# LAMEBOY.net
KiCad netlist of a schematic drawn in EAGLE
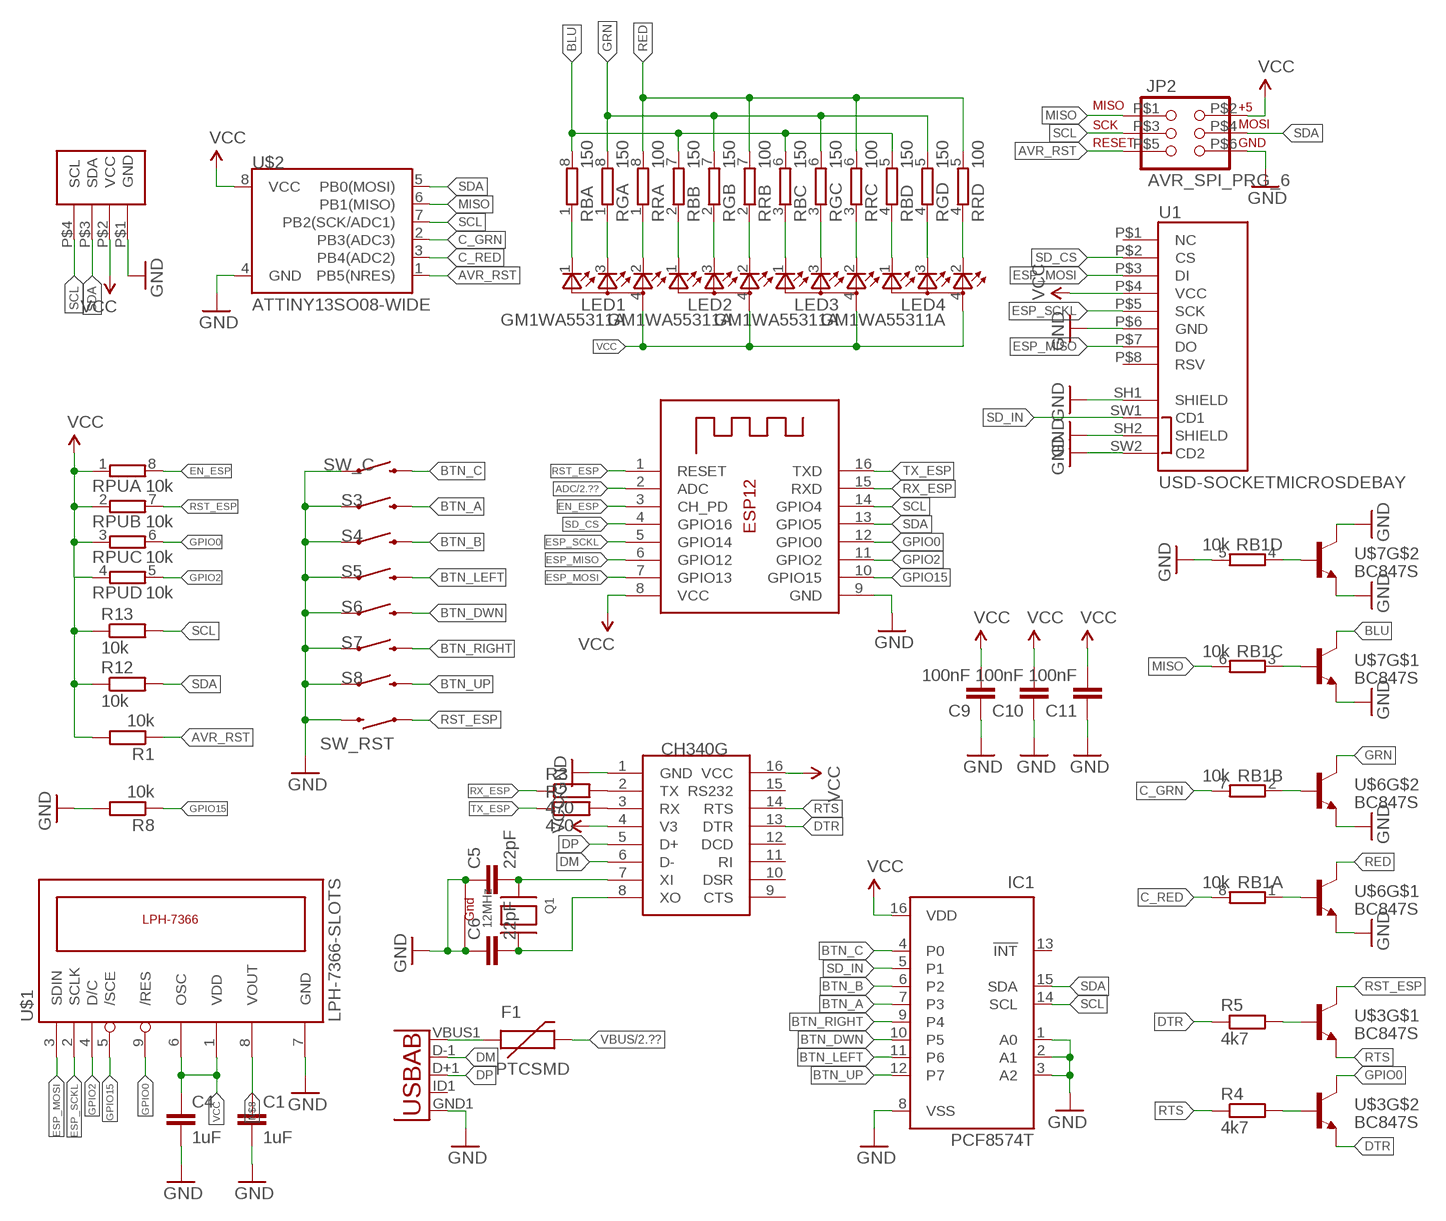
[diagram p0: schematic, sheet 1]
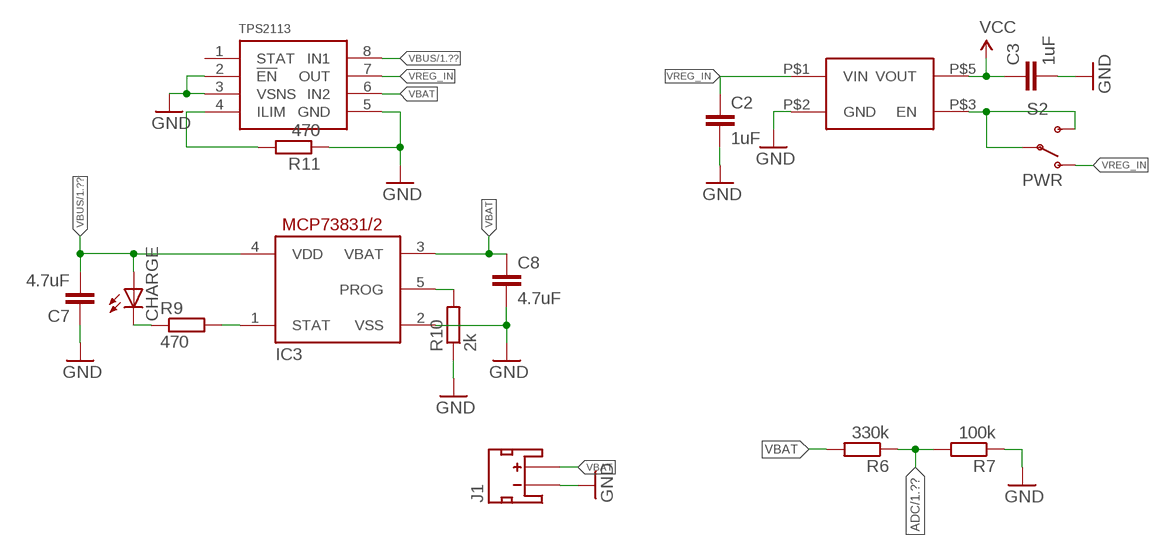
[diagram p1: schematic, sheet 2]

(export (version "E")
  (design (tool "Eeschema 10.0.6"))
  (components
    (comp (ref "C2")
      (value "1uF")
      (footprint "eagle-import:ONEFITSALL")
      (libsource (lib "eagle-import") (part "C-EUONEFITSALL"))
    )
    (comp (ref "C3")
      (value "1uF")
      (footprint "eagle-import:ONEFITSALL")
      (libsource (lib "eagle-import") (part "C-EUONEFITSALL"))
    )
    (comp (ref "C7")
      (value "4.7uF")
      (footprint "eagle-import:ONEFITSALL")
      (libsource (lib "eagle-import") (part "C-EUONEFITSALL"))
    )
    (comp (ref "C8")
      (value "4.7uF")
      (footprint "eagle-import:ONEFITSALL")
      (libsource (lib "eagle-import") (part "C-EUONEFITSALL"))
    )
    (comp (ref "CHARGE")
      (value "LEDCHARLIE")
      (footprint "eagle-import:CHIPLED_0603_CHARLIE")
      (libsource (lib "eagle-import") (part "LEDCHARLIE"))
    )
    (comp (ref "IC3")
      (value "MCP73831")
      (footprint "eagle-import:SOT23-5L")
      (libsource (lib "eagle-import") (part "MCP73831/OT"))
    )
    (comp (ref "J1")
      (value "JST_2MM_MALE")
      (footprint "eagle-import:JST-2-SMD")
      (libsource (lib "eagle-import") (part "JST_2MM_MALE"))
    )
    (comp (ref "R6")
      (value "330k")
      (footprint "eagle-import:ONEFITSALL")
      (libsource (lib "eagle-import") (part "R-EU_ONEFITSALL"))
    )
    (comp (ref "R7")
      (value "100k")
      (footprint "eagle-import:ONEFITSALL")
      (libsource (lib "eagle-import") (part "R-EU_ONEFITSALL"))
    )
    (comp (ref "R9")
      (value "470")
      (footprint "eagle-import:ONEFITSALL")
      (libsource (lib "eagle-import") (part "R-EU_ONEFITSALL"))
    )
    (comp (ref "R10")
      (value "2k")
      (footprint "eagle-import:ONEFITSALL")
      (libsource (lib "eagle-import") (part "R-EU_ONEFITSALL"))
    )
    (comp (ref "R11")
      (value "470")
      (footprint "eagle-import:ONEFITSALL")
      (libsource (lib "eagle-import") (part "R-EU_ONEFITSALL"))
    )
    (comp (ref "S2")
      (value "PWR")
      (footprint "eagle-import:SWITCH-SPST-SMD-A")
      (libsource (lib "eagle-import") (part "SWITCH-SPDT-SMD-A"))
    )
    (comp (ref "U$4")
      (value "TPS2113-PW")
      (footprint "eagle-import:TEXAS-PW")
      (libsource (lib "eagle-import") (part "TPS2113-PW"))
    )
    (comp (ref "U$9")
      (value "AP2112KAP2112K")
      (footprint "eagle-import:AP2112")
      (libsource (lib "eagle-import") (part "AP2112KAP2112K"))
    )
    (comp (ref "C1")
      (value "1uF")
      (footprint "eagle-import:ONEFITSALL")
      (libsource (lib "eagle-import") (part "C-EUONEFITSALL"))
    )
    (comp (ref "C4")
      (value "1uF")
      (footprint "eagle-import:ONEFITSALL")
      (libsource (lib "eagle-import") (part "C-EUONEFITSALL"))
    )
    (comp (ref "C5")
      (value "22pF")
      (footprint "eagle-import:ONEFITSALL")
      (libsource (lib "eagle-import") (part "C-EUONEFITSALL"))
    )
    (comp (ref "C6")
      (value "22pF")
      (footprint "eagle-import:ONEFITSALL")
      (libsource (lib "eagle-import") (part "C-EUONEFITSALL"))
    )
    (comp (ref "C9")
      (value "100nF")
      (footprint "eagle-import:ONEFITSALL")
      (libsource (lib "eagle-import") (part "C-EUONEFITSALL"))
    )
    (comp (ref "C10")
      (value "100nF")
      (footprint "eagle-import:ONEFITSALL")
      (libsource (lib "eagle-import") (part "C-EUONEFITSALL"))
    )
    (comp (ref "C11")
      (value "100nF")
      (footprint "eagle-import:ONEFITSALL")
      (libsource (lib "eagle-import") (part "C-EUONEFITSALL"))
    )
    (comp (ref "CH340G")
      (value "CH340GCH340G")
      (footprint "eagle-import:SOIC16")
      (libsource (lib "eagle-import") (part "CH340GCH340G"))
    )
    (comp (ref "F1")
      (value "PTCSMD")
      (footprint "eagle-import:PTC-1206")
      (libsource (lib "eagle-import") (part "PTCSMD"))
    )
    (comp (ref "IC1")
      (value "PCF8574T")
      (footprint "eagle-import:SO16W")
      (fields (field (name "MPN") "PCF8574T/3,512"))
      (libsource (lib "eagle-import") (part "PCF8574T"))
    )
    (comp (ref "JP2")
      (value "AVR_SPI_PRG_6")
      (footprint "eagle-import:2X3_SMD_PAD")
      (libsource (lib "eagle-import") (part "AVR_SPI_PRG_6"))
    )
    (comp (ref "LED1")
      (value "GM1WA55311A")
      (footprint "eagle-import:GM1WA55311A")
      (libsource (lib "eagle-import") (part "GM1WA55311A"))
    )
    (comp (ref "LED2")
      (value "GM1WA55311A")
      (footprint "eagle-import:GM1WA55311A")
      (libsource (lib "eagle-import") (part "GM1WA55311A"))
    )
    (comp (ref "LED3")
      (value "GM1WA55311A")
      (footprint "eagle-import:GM1WA55311A")
      (libsource (lib "eagle-import") (part "GM1WA55311A"))
    )
    (comp (ref "LED4")
      (value "GM1WA55311A")
      (footprint "eagle-import:GM1WA55311A")
      (libsource (lib "eagle-import") (part "GM1WA55311A"))
    )
    (comp (ref "Q1")
      (value "12MHz")
      (footprint "eagle-import:NX3225_BIGGER")
      (libsource (lib "eagle-import") (part "XTAL-4BIGGER"))
    )
    (comp (ref "R1")
      (value "10k")
      (footprint "eagle-import:ONEFITSALL")
      (libsource (lib "eagle-import") (part "R-EU_ONEFITSALL"))
    )
    (comp (ref "R2")
      (value "470")
      (footprint "eagle-import:ONEFITSALL")
      (libsource (lib "eagle-import") (part "R-EU_ONEFITSALL"))
    )
    (comp (ref "R3")
      (value "470")
      (footprint "eagle-import:ONEFITSALL")
      (libsource (lib "eagle-import") (part "R-EU_ONEFITSALL"))
    )
    (comp (ref "R4")
      (value "4k7")
      (footprint "eagle-import:ONEFITSALL")
      (libsource (lib "eagle-import") (part "R-EU_ONEFITSALL"))
    )
    (comp (ref "R5")
      (value "4k7")
      (footprint "eagle-import:ONEFITSALL")
      (libsource (lib "eagle-import") (part "R-EU_ONEFITSALL"))
    )
    (comp (ref "R8")
      (value "10k")
      (footprint "eagle-import:ONEFITSALL")
      (libsource (lib "eagle-import") (part "R-EU_ONEFITSALL"))
    )
    (comp (ref "R12")
      (value "10k")
      (footprint "eagle-import:ONEFITSALL")
      (libsource (lib "eagle-import") (part "R-EU_ONEFITSALL"))
    )
    (comp (ref "R13")
      (value "10k")
      (footprint "eagle-import:ONEFITSALL")
      (libsource (lib "eagle-import") (part "R-EU_ONEFITSALL"))
    )
    (comp (ref "RB")
      (value "150")
      (footprint "eagle-import:0603-ARC")
      (libsource (lib "eagle-import") (part "4R-N0603-ARC"))
    )
    (comp (ref "RB1")
      (value "10k")
      (footprint "eagle-import:0603-ARC")
      (libsource (lib "eagle-import") (part "4R-N0603-ARC"))
    )
    (comp (ref "RG")
      (value "150")
      (footprint "eagle-import:0603-ARC")
      (libsource (lib "eagle-import") (part "4R-N0603-ARC"))
    )
    (comp (ref "RPU")
      (value "10k")
      (footprint "eagle-import:0603-ARC")
      (libsource (lib "eagle-import") (part "4R-N0603-ARC"))
    )
    (comp (ref "RR")
      (value "100")
      (footprint "eagle-import:0603-ARC")
      (libsource (lib "eagle-import") (part "4R-N0603-ARC"))
    )
    (comp (ref "S3")
      (value "SWITCH-MOMENTARY-2SMD-4")
      (footprint "eagle-import:TACTILE_SWITCH_TALL")
      (libsource (lib "eagle-import") (part "SWITCH-MOMENTARY-2SMD-4"))
    )
    (comp (ref "S4")
      (value "SWITCH-MOMENTARY-2SMD-4")
      (footprint "eagle-import:TACTILE_SWITCH_TALL")
      (libsource (lib "eagle-import") (part "SWITCH-MOMENTARY-2SMD-4"))
    )
    (comp (ref "S5")
      (value "SWITCH-MOMENTARY-2SMD-4")
      (footprint "eagle-import:TACTILE_SWITCH_TALL")
      (libsource (lib "eagle-import") (part "SWITCH-MOMENTARY-2SMD-4"))
    )
    (comp (ref "S6")
      (value "SWITCH-MOMENTARY-2SMD-4")
      (footprint "eagle-import:TACTILE_SWITCH_TALL")
      (libsource (lib "eagle-import") (part "SWITCH-MOMENTARY-2SMD-4"))
    )
    (comp (ref "S7")
      (value "SWITCH-MOMENTARY-2SMD-4")
      (footprint "eagle-import:TACTILE_SWITCH_TALL")
      (libsource (lib "eagle-import") (part "SWITCH-MOMENTARY-2SMD-4"))
    )
    (comp (ref "S8")
      (value "SWITCH-MOMENTARY-2SMD-4")
      (footprint "eagle-import:TACTILE_SWITCH_TALL")
      (libsource (lib "eagle-import") (part "SWITCH-MOMENTARY-2SMD-4"))
    )
    (comp (ref "SW_C")
      (value "SWITCH-MOMENTARY-2-SMD-1101NE")
      (footprint "eagle-import:TACTILE-SWITCH-1101NE")
      (libsource (lib "eagle-import") (part "SWITCH-MOMENTARY-2-SMD-1101NE"))
    )
    (comp (ref "SW_RST")
      (value "SWITCH-MOMENTARY-2-SMD-1101NE")
      (footprint "eagle-import:TACTILE-SWITCH-1101NE")
      (libsource (lib "eagle-import") (part "SWITCH-MOMENTARY-2-SMD-1101NE"))
    )
    (comp (ref "U$1")
      (value "LPH-7366-SLOTS")
      (footprint "eagle-import:LPH-7366-SLOTS")
      (libsource (lib "eagle-import") (part "LPH-7366-SLOTS"))
    )
    (comp (ref "U$2")
      (value "ATTINY13SO08-WIDE")
      (footprint "eagle-import:SO08-EIAJ")
      (libsource (lib "eagle-import") (part "ATTINY13SO08-WIDE"))
    )
    (comp (ref "U$3")
      (value "BC847S")
      (footprint "eagle-import:SOT363")
      (libsource (lib "eagle-import") (part "MMDT3904"))
    )
    (comp (ref "U$6")
      (value "BC847S")
      (footprint "eagle-import:SOT363")
      (libsource (lib "eagle-import") (part "MMDT3904"))
    )
    (comp (ref "U$7")
      (value "BC847S")
      (footprint "eagle-import:SOT363")
      (libsource (lib "eagle-import") (part "MMDT3904"))
    )
    (comp (ref "U$10")
      (value "I2C_GROVE")
      (footprint "eagle-import:I2C_GROVE")
      (libsource (lib "eagle-import") (part "I2C_GROVE"))
    )
    (comp (ref "U1")
      (value "USD-SOCKETMICROSDEBAY")
      (footprint "eagle-import:MICRO-SD-SOCKET-EBAY")
      (libsource (lib "eagle-import") (part "USD-SOCKETMICROSDEBAY"))
    )
    (comp (ref "U2")
      (value "USB")
      (footprint "eagle-import:USB-AB-MICRO-SMD_V03")
      (libsource (lib "eagle-import") (part "USB-ABCONN-11794"))
    )
    (comp (ref "X1")
      (value "ESP-12")
      (footprint "eagle-import:ESP-12")
      (libsource (lib "eagle-import") (part "ESP-12"))
    )
  )
  (nets
    (net (code "1") (name "ADC") (class "Default")
      (node (ref "R6") (pin "P$1") (pinfunction "1_P$1") (pintype "passive"))
      (node (ref "R7") (pin "P$2") (pinfunction "2_P$2") (pintype "passive"))
      (node (ref "X1") (pin "2") (pinfunction "ADC_2") (pintype "passive"))
    )
    (net (code "2") (name "AVR_RST") (class "Default")
      (node (ref "JP2") (pin "P$5") (pinfunction "5_P$5") (pintype "passive"))
      (node (ref "R1") (pin "P$1") (pinfunction "1_P$1") (pintype "passive"))
      (node (ref "U$2") (pin "1") (pinfunction "PB5(NRES)_1") (pintype "bidirectional"))
    )
    (net (code "3") (name "BLU") (class "Default")
      (node (ref "RB") (pin "5") (pinfunction "2_5") (pintype "passive"))
      (node (ref "RB") (pin "6") (pinfunction "2_6") (pintype "passive"))
      (node (ref "RB") (pin "7") (pinfunction "2_7") (pintype "passive"))
      (node (ref "RB") (pin "8") (pinfunction "2_8") (pintype "passive"))
      (node (ref "U$7") (pin "3") (pinfunction "C_3") (pintype "passive"))
    )
    (net (code "4") (name "BTN_A") (class "Default")
      (node (ref "IC1") (pin "7") (pinfunction "P3_7") (pintype "bidirectional"))
      (node (ref "S3") (pin "B2") (pinfunction "2_B2") (pintype "passive"))
    )
    (net (code "5") (name "BTN_B") (class "Default")
      (node (ref "IC1") (pin "6") (pinfunction "P2_6") (pintype "bidirectional"))
      (node (ref "S4") (pin "B2") (pinfunction "2_B2") (pintype "passive"))
    )
    (net (code "6") (name "BTN_C") (class "Default")
      (node (ref "IC1") (pin "4") (pinfunction "P0_4") (pintype "bidirectional"))
      (node (ref "SW_C") (pin "P$2") (pinfunction "2_P$2") (pintype "passive"))
    )
    (net (code "7") (name "BTN_DWN") (class "Default")
      (node (ref "IC1") (pin "10") (pinfunction "P5_10") (pintype "bidirectional"))
      (node (ref "S6") (pin "B2") (pinfunction "2_B2") (pintype "passive"))
    )
    (net (code "8") (name "BTN_LEFT") (class "Default")
      (node (ref "IC1") (pin "11") (pinfunction "P6_11") (pintype "bidirectional"))
      (node (ref "S5") (pin "B2") (pinfunction "2_B2") (pintype "passive"))
    )
    (net (code "9") (name "BTN_RIGHT") (class "Default")
      (node (ref "IC1") (pin "9") (pinfunction "P4_9") (pintype "bidirectional"))
      (node (ref "S7") (pin "B2") (pinfunction "2_B2") (pintype "passive"))
    )
    (net (code "10") (name "BTN_UP") (class "Default")
      (node (ref "IC1") (pin "12") (pinfunction "P7_12") (pintype "bidirectional"))
      (node (ref "S8") (pin "B2") (pinfunction "2_B2") (pintype "passive"))
    )
    (net (code "11") (name "C_GRN") (class "Default")
      (node (ref "RB1") (pin "7") (pinfunction "2_7") (pintype "passive"))
      (node (ref "U$2") (pin "2") (pinfunction "PB3(ADC3)_2") (pintype "bidirectional"))
    )
    (net (code "12") (name "C_RED") (class "Default")
      (node (ref "RB1") (pin "8") (pinfunction "2_8") (pintype "passive"))
      (node (ref "U$2") (pin "3") (pinfunction "PB4(ADC2)_3") (pintype "bidirectional"))
    )
    (net (code "13") (name "DM") (class "Default")
      (node (ref "CH340G") (pin "6") (pinfunction "D-_6") (pintype "bidirectional"))
      (node (ref "U2") (pin "D-1") (pinfunction "D-_D-1") (pintype "bidirectional"))
    )
    (net (code "14") (name "DP") (class "Default")
      (node (ref "CH340G") (pin "5") (pinfunction "D+_5") (pintype "bidirectional"))
      (node (ref "U2") (pin "D+1") (pinfunction "D+_D+1") (pintype "bidirectional"))
    )
    (net (code "15") (name "DTR") (class "Default")
      (node (ref "CH340G") (pin "13") (pinfunction "DTR_13") (pintype "bidirectional"))
      (node (ref "R5") (pin "P$1") (pinfunction "1_P$1") (pintype "passive"))
      (node (ref "U$3") (pin "1") (pinfunction "E_1") (pintype "passive"))
    )
    (net (code "16") (name "EN_ESP") (class "Default")
      (node (ref "RPU") (pin "8") (pinfunction "2_8") (pintype "passive"))
      (node (ref "X1") (pin "3") (pinfunction "CH_PD_3") (pintype "input"))
    )
    (net (code "17") (name "ESP_MISO") (class "Default")
      (node (ref "U1") (pin "P$7") (pinfunction "DO_P$7") (pintype "bidirectional"))
      (node (ref "X1") (pin "6") (pinfunction "GPIO12_6") (pintype "bidirectional"))
    )
    (net (code "18") (name "ESP_MOSI") (class "Default")
      (node (ref "U$1") (pin "3") (pinfunction "SDIN_3") (pintype "input"))
      (node (ref "U1") (pin "P$3") (pinfunction "DI_P$3") (pintype "bidirectional"))
      (node (ref "X1") (pin "7") (pinfunction "GPIO13_7") (pintype "bidirectional"))
    )
    (net (code "19") (name "ESP_SCKL") (class "Default")
      (node (ref "U$1") (pin "2") (pinfunction "SCLK_2") (pintype "input"))
      (node (ref "U1") (pin "P$5") (pinfunction "SCK_P$5") (pintype "bidirectional"))
      (node (ref "X1") (pin "5") (pinfunction "GPIO14_5") (pintype "bidirectional"))
    )
    (net (code "20") (name "GND") (class "Default")
      (node (ref "C1") (pin "P$2") (pinfunction "2_P$2") (pintype "passive"))
      (node (ref "C10") (pin "P$1") (pinfunction "1_P$1") (pintype "passive"))
      (node (ref "C11") (pin "P$1") (pinfunction "1_P$1") (pintype "passive"))
      (node (ref "C2") (pin "P$2") (pinfunction "2_P$2") (pintype "passive"))
      (node (ref "C3") (pin "P$2") (pinfunction "2_P$2") (pintype "passive"))
      (node (ref "C4") (pin "P$2") (pinfunction "2_P$2") (pintype "passive"))
      (node (ref "C5") (pin "P$1") (pinfunction "1_P$1") (pintype "passive"))
      (node (ref "C6") (pin "P$1") (pinfunction "1_P$1") (pintype "passive"))
      (node (ref "C7") (pin "P$1") (pinfunction "1_P$1") (pintype "passive"))
      (node (ref "C8") (pin "P$2") (pinfunction "2_P$2") (pintype "passive"))
      (node (ref "C9") (pin "P$1") (pinfunction "1_P$1") (pintype "passive"))
      (node (ref "CH340G") (pin "1") (pinfunction "GND_1") (pintype "bidirectional"))
      (node (ref "IC1") (pin "1") (pinfunction "A0_1") (pintype "input"))
      (node (ref "IC1") (pin "2") (pinfunction "A1_2") (pintype "input"))
      (node (ref "IC1") (pin "3") (pinfunction "A2_3") (pintype "input"))
      (node (ref "IC1") (pin "8") (pinfunction "VSS_8") (pintype "power_in"))
      (node (ref "IC3") (pin "2") (pinfunction "VSS_2") (pintype "power_in"))
      (node (ref "J1") (pin "1") (pinfunction "-_1") (pintype "bidirectional"))
      (node (ref "JP2") (pin "P$6") (pinfunction "6_P$6") (pintype "passive"))
      (node (ref "Q1") (pin "2") (pinfunction "G2_2") (pintype "power_in"))
      (node (ref "Q1") (pin "4") (pinfunction "G1_4") (pintype "power_in"))
      (node (ref "R10") (pin "P$1") (pinfunction "1_P$1") (pintype "passive"))
      (node (ref "R11") (pin "P$1") (pinfunction "1_P$1") (pintype "passive"))
      (node (ref "R7") (pin "P$1") (pinfunction "1_P$1") (pintype "passive"))
      (node (ref "R8") (pin "P$2") (pinfunction "2_P$2") (pintype "passive"))
      (node (ref "RB1") (pin "5") (pinfunction "2_5") (pintype "passive"))
      (node (ref "S3") (pin "A2") (pinfunction "1_A2") (pintype "passive"))
      (node (ref "S4") (pin "A2") (pinfunction "1_A2") (pintype "passive"))
      (node (ref "S5") (pin "A2") (pinfunction "1_A2") (pintype "passive"))
      (node (ref "S6") (pin "A2") (pinfunction "1_A2") (pintype "passive"))
      (node (ref "S7") (pin "A2") (pinfunction "1_A2") (pintype "passive"))
      (node (ref "S8") (pin "A2") (pinfunction "1_A2") (pintype "passive"))
      (node (ref "SW_C") (pin "P$1") (pinfunction "1_P$1") (pintype "passive"))
      (node (ref "SW_RST") (pin "P$2") (pinfunction "2_P$2") (pintype "passive"))
      (node (ref "U$1") (pin "7") (pinfunction "GND_7") (pintype "power_in"))
      (node (ref "U$10") (pin "P$1") (pinfunction "GND_P$1") (pintype "bidirectional"))
      (node (ref "U$2") (pin "4") (pinfunction "GND_4") (pintype "bidirectional"))
      (node (ref "U$4") (pin "2") (pinfunction "~{EN}_2") (pintype "bidirectional"))
      (node (ref "U$4") (pin "3") (pinfunction "VSNS_3") (pintype "bidirectional"))
      (node (ref "U$4") (pin "5") (pinfunction "GND_5") (pintype "bidirectional"))
      (node (ref "U$6") (pin "1") (pinfunction "E_1") (pintype "passive"))
      (node (ref "U$6") (pin "4") (pinfunction "E_4") (pintype "passive"))
      (node (ref "U$7") (pin "1") (pinfunction "E_1") (pintype "passive"))
      (node (ref "U$7") (pin "4") (pinfunction "E_4") (pintype "passive"))
      (node (ref "U$7") (pin "6") (pinfunction "C_6") (pintype "passive"))
      (node (ref "U$9") (pin "P$2") (pinfunction "GND_P$2") (pintype "bidirectional"))
      (node (ref "U1") (pin "P$6") (pinfunction "GND_P$6") (pintype "bidirectional"))
      (node (ref "U1") (pin "SH1") (pinfunction "SHIELD_SH1") (pintype "bidirectional"))
      (node (ref "U1") (pin "SH2") (pinfunction "SHIELD_SH2") (pintype "bidirectional"))
      (node (ref "U1") (pin "SW2") (pinfunction "CD2_SW2") (pintype "bidirectional"))
      (node (ref "U2") (pin "GND1") (pinfunction "GND_GND1") (pintype "bidirectional"))
      (node (ref "X1") (pin "9") (pinfunction "GND_9") (pintype "power_in"))
    )
    (net (code "21") (name "GPIO0") (class "Default")
      (node (ref "RPU") (pin "6") (pinfunction "2_6") (pintype "passive"))
      (node (ref "U$1") (pin "9") (pinfunction "/RES_9") (pintype "input"))
      (node (ref "U$3") (pin "6") (pinfunction "C_6") (pintype "passive"))
      (node (ref "X1") (pin "12") (pinfunction "GPIO0_12") (pintype "bidirectional"))
    )
    (net (code "22") (name "GPIO2") (class "Default")
      (node (ref "RPU") (pin "5") (pinfunction "2_5") (pintype "passive"))
      (node (ref "U$1") (pin "4") (pinfunction "D/C_4") (pintype "input"))
      (node (ref "X1") (pin "11") (pinfunction "GPIO2_11") (pintype "bidirectional"))
    )
    (net (code "23") (name "GPIO15") (class "Default")
      (node (ref "R8") (pin "P$1") (pinfunction "1_P$1") (pintype "passive"))
      (node (ref "U$1") (pin "5") (pinfunction "/SCE_5") (pintype "input"))
      (node (ref "X1") (pin "10") (pinfunction "GPIO15_10") (pintype "bidirectional"))
    )
    (net (code "24") (name "GRN") (class "Default")
      (node (ref "RG") (pin "5") (pinfunction "2_5") (pintype "passive"))
      (node (ref "RG") (pin "6") (pinfunction "2_6") (pintype "passive"))
      (node (ref "RG") (pin "7") (pinfunction "2_7") (pintype "passive"))
      (node (ref "RG") (pin "8") (pinfunction "2_8") (pintype "passive"))
      (node (ref "U$6") (pin "6") (pinfunction "C_6") (pintype "passive"))
    )
    (net (code "25") (name "MISO") (class "Default")
      (node (ref "JP2") (pin "P$1") (pinfunction "1_P$1") (pintype "passive"))
      (node (ref "RB1") (pin "6") (pinfunction "2_6") (pintype "passive"))
      (node (ref "U$2") (pin "6") (pinfunction "PB1(MISO)_6") (pintype "bidirectional"))
    )
    (net (code "26") (name "N$8") (class "Default")
      (node (ref "C1") (pin "P$1") (pinfunction "1_P$1") (pintype "passive"))
      (node (ref "U$1") (pin "8") (pinfunction "VOUT_8") (pintype "passive"))
    )
    (net (code "27") (name "Net-(C5-2)") (class "Default")
      (node (ref "C5") (pin "P$2") (pinfunction "2_P$2") (pintype "passive"))
      (node (ref "CH340G") (pin "7") (pinfunction "XI_7") (pintype "bidirectional"))
      (node (ref "Q1") (pin "1") (pinfunction "X1_1") (pintype "bidirectional"))
    )
    (net (code "28") (name "Net-(C6-2)") (class "Default")
      (node (ref "C6") (pin "P$2") (pinfunction "2_P$2") (pintype "passive"))
      (node (ref "CH340G") (pin "8") (pinfunction "XO_8") (pintype "bidirectional"))
      (node (ref "Q1") (pin "3") (pinfunction "X2_3") (pintype "bidirectional"))
    )
    (net (code "29") (name "Net-(CH340G-RX)") (class "Default")
      (node (ref "CH340G") (pin "3") (pinfunction "RX_3") (pintype "bidirectional"))
      (node (ref "R2") (pin "P$2") (pinfunction "2_P$2") (pintype "passive"))
    )
    (net (code "30") (name "Net-(CH340G-TX)") (class "Default")
      (node (ref "CH340G") (pin "2") (pinfunction "TX_2") (pintype "bidirectional"))
      (node (ref "R3") (pin "P$2") (pinfunction "2_P$2") (pintype "passive"))
    )
    (net (code "31") (name "Net-(IC3-PROG)") (class "Default")
      (node (ref "IC3") (pin "5") (pinfunction "PROG_5") (pintype "input"))
      (node (ref "R10") (pin "P$2") (pinfunction "2_P$2") (pintype "passive"))
    )
    (net (code "32") (name "Net-(IC3-STAT)") (class "Default")
      (node (ref "IC3") (pin "1") (pinfunction "STAT_1") (pintype "output"))
      (node (ref "R9") (pin "P$2") (pinfunction "2_P$2") (pintype "passive"))
    )
    (net (code "33") (name "Net-(LED1-CBLUE)") (class "Default")
      (node (ref "LED1") (pin "3") (pinfunction "CBLUE_3") (pintype "passive"))
      (node (ref "RG") (pin "1") (pinfunction "1_1") (pintype "passive"))
    )
    (net (code "34") (name "Net-(LED1-CGREEN)") (class "Default")
      (node (ref "LED1") (pin "1") (pinfunction "CGREEN_1") (pintype "passive"))
      (node (ref "RB") (pin "1") (pinfunction "1_1") (pintype "passive"))
    )
    (net (code "35") (name "Net-(LED1-CRED)") (class "Default")
      (node (ref "LED1") (pin "2") (pinfunction "CRED_2") (pintype "passive"))
      (node (ref "RR") (pin "1") (pinfunction "1_1") (pintype "passive"))
    )
    (net (code "36") (name "Net-(LED2-CBLUE)") (class "Default")
      (node (ref "LED2") (pin "3") (pinfunction "CBLUE_3") (pintype "passive"))
      (node (ref "RG") (pin "2") (pinfunction "1_2") (pintype "passive"))
    )
    (net (code "37") (name "Net-(LED2-CGREEN)") (class "Default")
      (node (ref "LED2") (pin "1") (pinfunction "CGREEN_1") (pintype "passive"))
      (node (ref "RB") (pin "2") (pinfunction "1_2") (pintype "passive"))
    )
    (net (code "38") (name "Net-(LED2-CRED)") (class "Default")
      (node (ref "LED2") (pin "2") (pinfunction "CRED_2") (pintype "passive"))
      (node (ref "RR") (pin "2") (pinfunction "1_2") (pintype "passive"))
    )
    (net (code "39") (name "Net-(LED3-CBLUE)") (class "Default")
      (node (ref "LED3") (pin "3") (pinfunction "CBLUE_3") (pintype "passive"))
      (node (ref "RG") (pin "3") (pinfunction "1_3") (pintype "passive"))
    )
    (net (code "40") (name "Net-(LED3-CGREEN)") (class "Default")
      (node (ref "LED3") (pin "1") (pinfunction "CGREEN_1") (pintype "passive"))
      (node (ref "RB") (pin "3") (pinfunction "1_3") (pintype "passive"))
    )
    (net (code "41") (name "Net-(LED3-CRED)") (class "Default")
      (node (ref "LED3") (pin "2") (pinfunction "CRED_2") (pintype "passive"))
      (node (ref "RR") (pin "3") (pinfunction "1_3") (pintype "passive"))
    )
    (net (code "42") (name "Net-(LED4-CBLUE)") (class "Default")
      (node (ref "LED4") (pin "3") (pinfunction "CBLUE_3") (pintype "passive"))
      (node (ref "RG") (pin "4") (pinfunction "1_4") (pintype "passive"))
    )
    (net (code "43") (name "Net-(LED4-CGREEN)") (class "Default")
      (node (ref "LED4") (pin "1") (pinfunction "CGREEN_1") (pintype "passive"))
      (node (ref "RB") (pin "4") (pinfunction "1_4") (pintype "passive"))
    )
    (net (code "44") (name "Net-(LED4-CRED)") (class "Default")
      (node (ref "LED4") (pin "2") (pinfunction "CRED_2") (pintype "passive"))
      (node (ref "RR") (pin "4") (pinfunction "1_4") (pintype "passive"))
    )
    (net (code "45") (name "Net-(R4-2)") (class "Default")
      (node (ref "R4") (pin "P$2") (pinfunction "2_P$2") (pintype "passive"))
      (node (ref "U$3") (pin "2") (pinfunction "B_2") (pintype "passive"))
    )
    (net (code "46") (name "Net-(R5-2)") (class "Default")
      (node (ref "R5") (pin "P$2") (pinfunction "2_P$2") (pintype "passive"))
      (node (ref "U$3") (pin "5") (pinfunction "B_5") (pintype "passive"))
    )
    (net (code "47") (name "Net-(R9-1)") (class "Default")
      (node (ref "CHARGE") (pin "C") (pinfunction "C_C") (pintype "passive"))
      (node (ref "R9") (pin "P$1") (pinfunction "1_P$1") (pintype "passive"))
    )
    (net (code "48") (name "Net-(R11-2)") (class "Default")
      (node (ref "R11") (pin "P$2") (pinfunction "2_P$2") (pintype "passive"))
      (node (ref "U$4") (pin "4") (pinfunction "ILIM_4") (pintype "bidirectional"))
    )
    (net (code "49") (name "Net-(RB1B-1)") (class "Default")
      (node (ref "RB1") (pin "2") (pinfunction "1_2") (pintype "passive"))
      (node (ref "U$6") (pin "2") (pinfunction "B_2") (pintype "passive"))
    )
    (net (code "50") (name "Net-(RB1C-1)") (class "Default")
      (node (ref "RB1") (pin "3") (pinfunction "1_3") (pintype "passive"))
      (node (ref "U$7") (pin "5") (pinfunction "B_5") (pintype "passive"))
    )
    (net (code "51") (name "Net-(RB1D-1)") (class "Default")
      (node (ref "RB1") (pin "4") (pinfunction "1_4") (pintype "passive"))
      (node (ref "U$7") (pin "2") (pinfunction "B_2") (pintype "passive"))
    )
    (net (code "52") (name "Net-(S2-P)") (class "Default")
      (node (ref "S2") (pin "2") (pinfunction "P_2") (pintype "passive"))
      (node (ref "S2") (pin "3") (pinfunction "S_3") (pintype "passive"))
      (node (ref "U$9") (pin "P$3") (pinfunction "EN_P$3") (pintype "bidirectional"))
    )
    (net (code "53") (name "Net-(U$6A-B)") (class "Default")
      (node (ref "RB1") (pin "1") (pinfunction "1_1") (pintype "passive"))
      (node (ref "U$6") (pin "5") (pinfunction "B_5") (pintype "passive"))
    )
    (net (code "54") (name "Net-(U2-VBUS)") (class "Default")
      (node (ref "F1") (pin "1") (pinfunction "1_1") (pintype "bidirectional"))
      (node (ref "U2") (pin "VBUS1") (pinfunction "VBUS_VBUS1") (pintype "bidirectional"))
    )
    (net (code "55") (name "RED") (class "Default")
      (node (ref "RR") (pin "5") (pinfunction "2_5") (pintype "passive"))
      (node (ref "RR") (pin "6") (pinfunction "2_6") (pintype "passive"))
      (node (ref "RR") (pin "7") (pinfunction "2_7") (pintype "passive"))
      (node (ref "RR") (pin "8") (pinfunction "2_8") (pintype "passive"))
      (node (ref "U$6") (pin "3") (pinfunction "C_3") (pintype "passive"))
    )
    (net (code "56") (name "RST_ESP") (class "Default")
      (node (ref "RPU") (pin "7") (pinfunction "2_7") (pintype "passive"))
      (node (ref "SW_RST") (pin "P$1") (pinfunction "1_P$1") (pintype "passive"))
      (node (ref "U$3") (pin "3") (pinfunction "C_3") (pintype "passive"))
      (node (ref "X1") (pin "1") (pinfunction "RESET_1") (pintype "input"))
    )
    (net (code "57") (name "RTS") (class "Default")
      (node (ref "CH340G") (pin "14") (pinfunction "RTS_14") (pintype "bidirectional"))
      (node (ref "R4") (pin "P$1") (pinfunction "1_P$1") (pintype "passive"))
      (node (ref "U$3") (pin "4") (pinfunction "E_4") (pintype "passive"))
    )
    (net (code "58") (name "RX_ESP") (class "Default")
      (node (ref "R3") (pin "P$1") (pinfunction "1_P$1") (pintype "passive"))
      (node (ref "X1") (pin "15") (pinfunction "RXD_15") (pintype "input"))
    )
    (net (code "59") (name "SCL") (class "Default")
      (node (ref "IC1") (pin "14") (pinfunction "SCL_14") (pintype "input"))
      (node (ref "JP2") (pin "P$3") (pinfunction "3_P$3") (pintype "passive"))
      (node (ref "R13") (pin "P$2") (pinfunction "2_P$2") (pintype "passive"))
      (node (ref "U$10") (pin "P$4") (pinfunction "SCL_P$4") (pintype "bidirectional"))
      (node (ref "U$2") (pin "7") (pinfunction "PB2(SCK/ADC1)_7") (pintype "bidirectional"))
      (node (ref "X1") (pin "14") (pinfunction "GPIO4_14") (pintype "bidirectional"))
    )
    (net (code "60") (name "SDA") (class "Default")
      (node (ref "IC1") (pin "15") (pinfunction "SDA_15") (pintype "bidirectional"))
      (node (ref "JP2") (pin "P$4") (pinfunction "4_P$4") (pintype "passive"))
      (node (ref "R12") (pin "P$2") (pinfunction "2_P$2") (pintype "passive"))
      (node (ref "U$10") (pin "P$3") (pinfunction "SDA_P$3") (pintype "bidirectional"))
      (node (ref "U$2") (pin "5") (pinfunction "PB0(MOSI)_5") (pintype "bidirectional"))
      (node (ref "X1") (pin "13") (pinfunction "GPIO5_13") (pintype "bidirectional"))
    )
    (net (code "61") (name "SD_CS") (class "Default")
      (node (ref "U1") (pin "P$2") (pinfunction "CS_P$2") (pintype "bidirectional"))
      (node (ref "X1") (pin "4") (pinfunction "GPIO16_4") (pintype "bidirectional"))
    )
    (net (code "62") (name "SD_IN") (class "Default")
      (node (ref "IC1") (pin "5") (pinfunction "P1_5") (pintype "bidirectional"))
      (node (ref "U1") (pin "SW1") (pinfunction "CD1_SW1") (pintype "bidirectional"))
    )
    (net (code "63") (name "TX_ESP") (class "Default")
      (node (ref "R2") (pin "P$1") (pinfunction "1_P$1") (pintype "passive"))
      (node (ref "X1") (pin "16") (pinfunction "TXD_16") (pintype "output"))
    )
    (net (code "64") (name "VBAT") (class "Default")
      (node (ref "C8") (pin "P$1") (pinfunction "1_P$1") (pintype "passive"))
      (node (ref "IC3") (pin "3") (pinfunction "VBAT_3") (pintype "bidirectional"))
      (node (ref "J1") (pin "2") (pinfunction "+_2") (pintype "bidirectional"))
      (node (ref "R6") (pin "P$2") (pinfunction "2_P$2") (pintype "passive"))
      (node (ref "U$4") (pin "6") (pinfunction "IN2_6") (pintype "bidirectional"))
    )
    (net (code "65") (name "VBUS") (class "Default")
      (node (ref "C7") (pin "P$2") (pinfunction "2_P$2") (pintype "passive"))
      (node (ref "CHARGE") (pin "A") (pinfunction "A_A") (pintype "passive"))
      (node (ref "F1") (pin "2") (pinfunction "2_2") (pintype "bidirectional"))
      (node (ref "IC3") (pin "4") (pinfunction "VDD_4") (pintype "power_in"))
      (node (ref "U$4") (pin "8") (pinfunction "IN1_8") (pintype "bidirectional"))
    )
    (net (code "66") (name "VCC") (class "Default")
      (node (ref "C10") (pin "P$2") (pinfunction "2_P$2") (pintype "passive"))
      (node (ref "C11") (pin "P$2") (pinfunction "2_P$2") (pintype "passive"))
      (node (ref "C3") (pin "P$1") (pinfunction "1_P$1") (pintype "passive"))
      (node (ref "C4") (pin "P$1") (pinfunction "1_P$1") (pintype "passive"))
      (node (ref "C9") (pin "P$2") (pinfunction "2_P$2") (pintype "passive"))
      (node (ref "CH340G") (pin "16") (pinfunction "VCC_16") (pintype "bidirectional"))
      (node (ref "CH340G") (pin "4") (pinfunction "V3_4") (pintype "bidirectional"))
      (node (ref "IC1") (pin "16") (pinfunction "VDD_16") (pintype "power_in"))
      (node (ref "JP2") (pin "P$2") (pinfunction "2_P$2") (pintype "passive"))
      (node (ref "LED1") (pin "4") (pinfunction "A_4") (pintype "passive"))
      (node (ref "LED2") (pin "4") (pinfunction "A_4") (pintype "passive"))
      (node (ref "LED3") (pin "4") (pinfunction "A_4") (pintype "passive"))
      (node (ref "LED4") (pin "4") (pinfunction "A_4") (pintype "passive"))
      (node (ref "R1") (pin "P$2") (pinfunction "2_P$2") (pintype "passive"))
      (node (ref "R12") (pin "P$1") (pinfunction "1_P$1") (pintype "passive"))
      (node (ref "R13") (pin "P$1") (pinfunction "1_P$1") (pintype "passive"))
      (node (ref "RPU") (pin "1") (pinfunction "1_1") (pintype "passive"))
      (node (ref "RPU") (pin "2") (pinfunction "1_2") (pintype "passive"))
      (node (ref "RPU") (pin "3") (pinfunction "1_3") (pintype "passive"))
      (node (ref "RPU") (pin "4") (pinfunction "1_4") (pintype "passive"))
      (node (ref "U$1") (pin "1") (pinfunction "VDD_1") (pintype "power_in"))
      (node (ref "U$1") (pin "6") (pinfunction "OSC_6") (pintype "passive"))
      (node (ref "U$10") (pin "P$2") (pinfunction "VCC_P$2") (pintype "bidirectional"))
      (node (ref "U$2") (pin "8") (pinfunction "VCC_8") (pintype "bidirectional"))
      (node (ref "U$9") (pin "P$5") (pinfunction "VOUT_P$5") (pintype "bidirectional"))
      (node (ref "U1") (pin "P$4") (pinfunction "VCC_P$4") (pintype "bidirectional"))
      (node (ref "X1") (pin "8") (pinfunction "VCC_8") (pintype "power_in"))
    )
    (net (code "67") (name "VREG_IN") (class "Default")
      (node (ref "C2") (pin "P$1") (pinfunction "1_P$1") (pintype "passive"))
      (node (ref "S2") (pin "1") (pinfunction "O_1") (pintype "passive"))
      (node (ref "U$4") (pin "7") (pinfunction "OUT_7") (pintype "bidirectional"))
      (node (ref "U$9") (pin "P$1") (pinfunction "VIN_P$1") (pintype "bidirectional"))
    )
    (net (code "68") (name "unconnected-(CH340G-CTS-Pad9)") (class "Default")
      (node (ref "CH340G") (pin "9") (pinfunction "CTS_9") (pintype "bidirectional"))
    )
    (net (code "69") (name "unconnected-(CH340G-DCD-Pad12)") (class "Default")
      (node (ref "CH340G") (pin "12") (pinfunction "DCD_12") (pintype "bidirectional"))
    )
    (net (code "70") (name "unconnected-(CH340G-DSR-Pad10)") (class "Default")
      (node (ref "CH340G") (pin "10") (pinfunction "DSR_10") (pintype "bidirectional"))
    )
    (net (code "71") (name "unconnected-(CH340G-RI-Pad11)") (class "Default")
      (node (ref "CH340G") (pin "11") (pinfunction "RI_11") (pintype "bidirectional"))
    )
    (net (code "72") (name "unconnected-(CH340G-RS232-Pad15)") (class "Default")
      (node (ref "CH340G") (pin "15") (pinfunction "RS232_15") (pintype "bidirectional"))
    )
    (net (code "73") (name "unconnected-(IC1-~{INT}-Pad13)") (class "Default")
      (node (ref "IC1") (pin "13") (pinfunction "~{INT}_13") (pintype "output"))
    )
    (net (code "74") (name "unconnected-(J1-PAD1-PadNC1)") (class "Default")
      (node (ref "J1") (pin "NC1") (pinfunction "PAD1_NC1") (pintype "bidirectional"))
    )
    (net (code "75") (name "unconnected-(J1-PAD2-PadNC2)") (class "Default")
      (node (ref "J1") (pin "NC2") (pinfunction "PAD2_NC2") (pintype "bidirectional"))
    )
    (net (code "76") (name "unconnected-(U$4-STAT-Pad1)") (class "Default")
      (node (ref "U$4") (pin "1") (pinfunction "STAT_1") (pintype "bidirectional"))
    )
    (net (code "77") (name "unconnected-(U1-NC-PadP$1)") (class "Default")
      (node (ref "U1") (pin "P$1") (pinfunction "NC_P$1") (pintype "bidirectional"))
    )
    (net (code "78") (name "unconnected-(U1-RSV-PadP$8)") (class "Default")
      (node (ref "U1") (pin "P$8") (pinfunction "RSV_P$8") (pintype "bidirectional"))
    )
    (net (code "79") (name "unconnected-(U2-USBID-PadID1)") (class "Default")
      (node (ref "U2") (pin "ID1") (pinfunction "USBID_ID1") (pintype "bidirectional"))
    )
  )
)
